# Qwiic_High_Performance_Magnetometer_X01.net
KiCad netlist of a schematic drawn in EAGLE
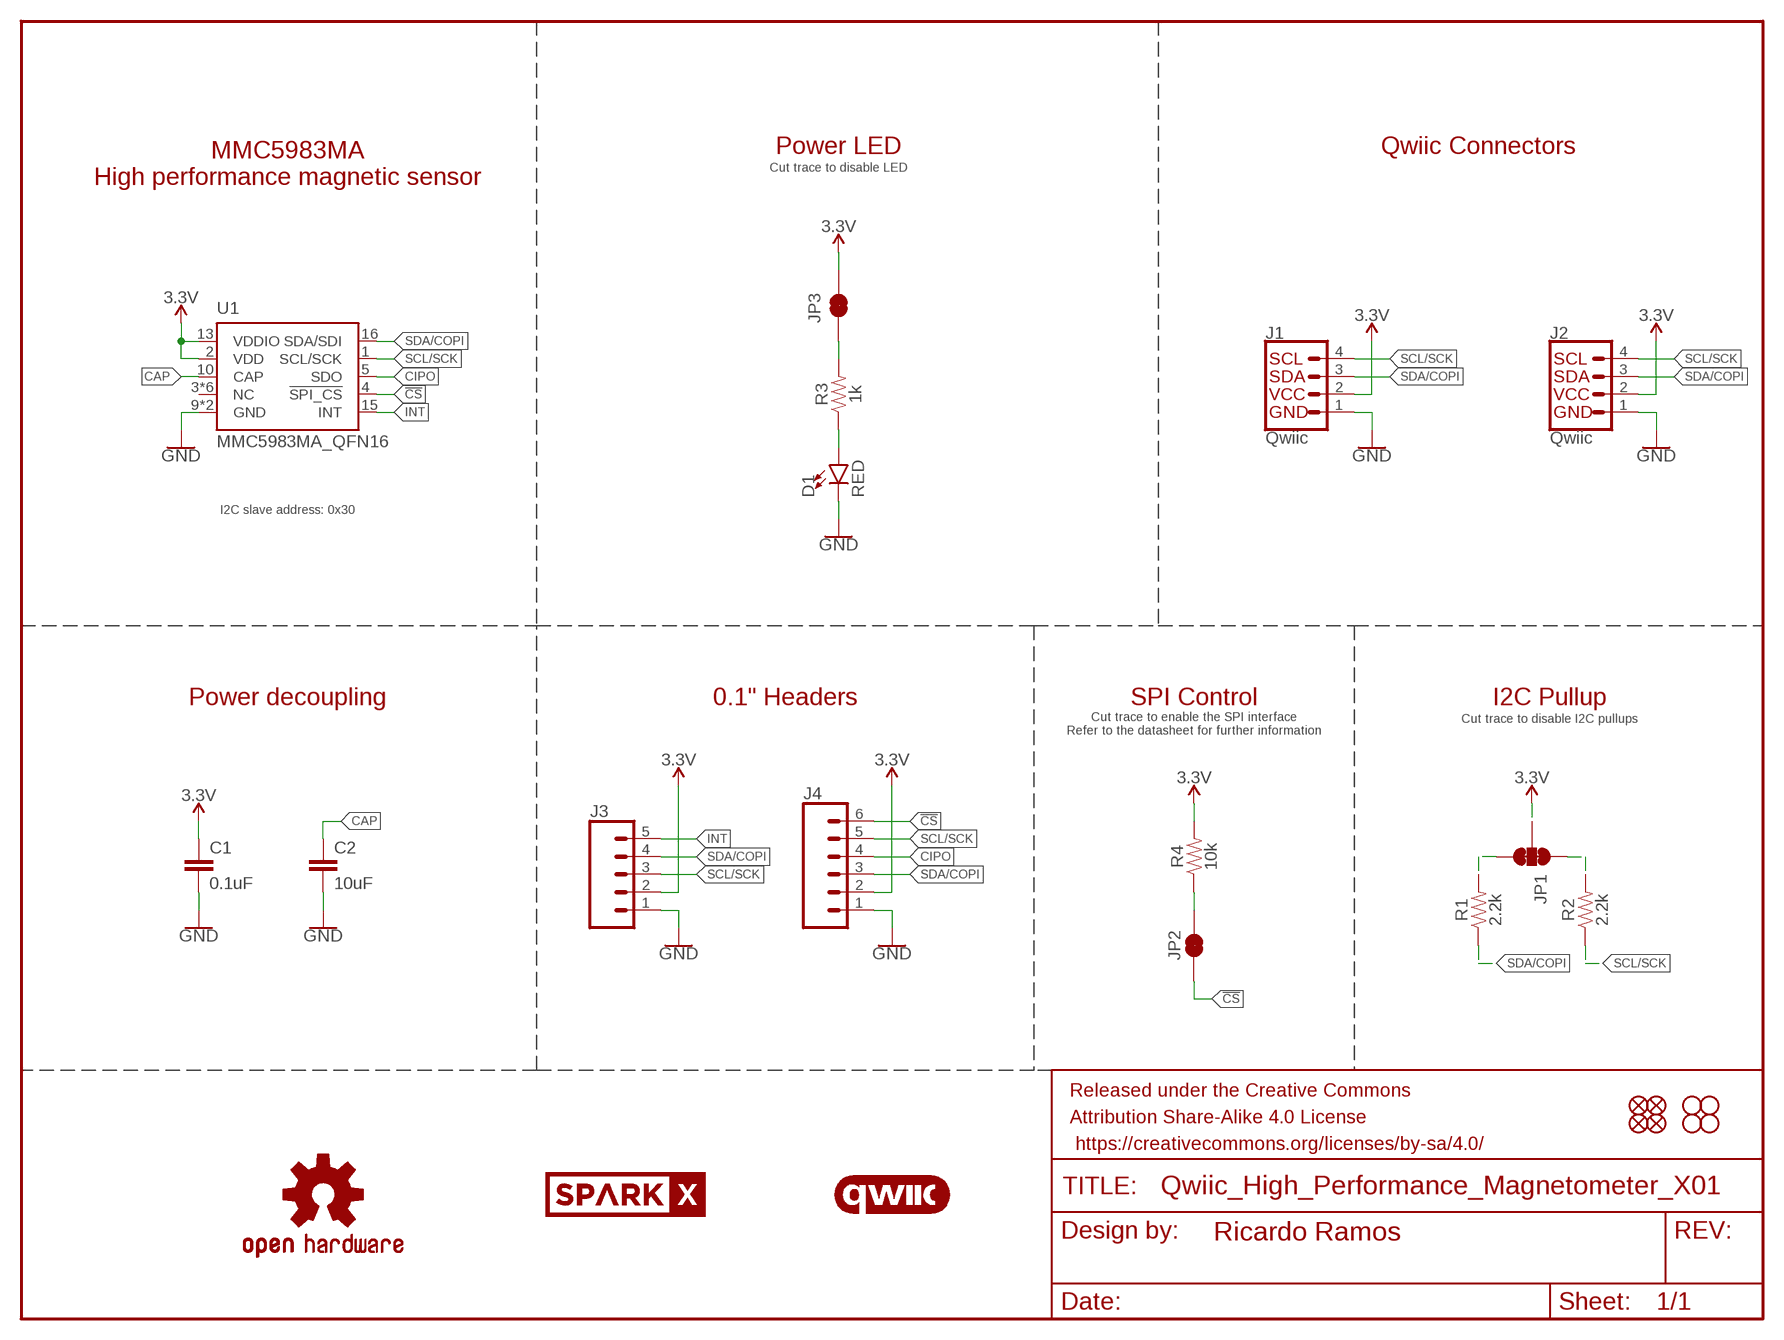
[diagram p0: schematic, sheet 1]

(export (version "E")
  (design (tool "Eeschema 10.0.6"))
  (components
    (comp (ref "C1")
      (value "0.1uF")
      (footprint "eagle-import:0603")
      (libsource (lib "eagle-import") (part "0.1UF-0603-25V-(+80/-20%)"))
    )
    (comp (ref "C2")
      (value "10uF")
      (footprint "eagle-import:0603")
      (libsource (lib "eagle-import") (part "10UF-0603-6.3V-20%"))
    )
    (comp (ref "D1")
      (value "RED")
      (footprint "eagle-import:LED-0603")
      (libsource (lib "eagle-import") (part "LED-RED0603"))
    )
    (comp (ref "FD1")
      (value "FIDUCIAL1X2")
      (footprint "eagle-import:FIDUCIAL-1X2")
      (libsource (lib "eagle-import") (part "FIDUCIAL1X2"))
    )
    (comp (ref "FD2")
      (value "FIDUCIAL1X2")
      (footprint "eagle-import:FIDUCIAL-1X2")
      (libsource (lib "eagle-import") (part "FIDUCIAL1X2"))
    )
    (comp (ref "FD3")
      (value "FIDUCIAL1X2")
      (footprint "eagle-import:FIDUCIAL-1X2")
      (libsource (lib "eagle-import") (part "FIDUCIAL1X2"))
    )
    (comp (ref "FD4")
      (value "FIDUCIAL1X2")
      (footprint "eagle-import:FIDUCIAL-1X2")
      (libsource (lib "eagle-import") (part "FIDUCIAL1X2"))
    )
    (comp (ref "FRAME1")
      (value "FRAME-LETTERNO_PACKAGE")
      (footprint "eagle-import:DUMMY")
      (fields (field (name "DESIGNER") "Ricardo Ramos") (field (name "DESIGNER_1") "Ricardo Ramos"))
      (libsource (lib "eagle-import") (part "FRAME-LETTERNO_PACKAGE"))
    )
    (comp (ref "H1")
      (value "STAND-OFF")
      (footprint "eagle-import:STAND-OFF")
      (libsource (lib "eagle-import") (part "STAND-OFF"))
    )
    (comp (ref "H2")
      (value "STAND-OFF")
      (footprint "eagle-import:STAND-OFF")
      (libsource (lib "eagle-import") (part "STAND-OFF"))
    )
    (comp (ref "H3")
      (value "STAND-OFF")
      (footprint "eagle-import:STAND-OFF")
      (libsource (lib "eagle-import") (part "STAND-OFF"))
    )
    (comp (ref "H4")
      (value "STAND-OFF")
      (footprint "eagle-import:STAND-OFF")
      (libsource (lib "eagle-import") (part "STAND-OFF"))
    )
    (comp (ref "J1")
      (value "Qwiic")
      (footprint "eagle-import:JST04_1MM_RA")
      (libsource (lib "eagle-import") (part "QWIIC_CONNECTORJS-1MM"))
    )
    (comp (ref "J2")
      (value "Qwiic")
      (footprint "eagle-import:JST04_1MM_RA")
      (libsource (lib "eagle-import") (part "QWIIC_CONNECTORJS-1MM"))
    )
    (comp (ref "J3")
      (value "CONN_05NO_SILK")
      (footprint "eagle-import:1X05_NO_SILK")
      (libsource (lib "eagle-import") (part "CONN_05NO_SILK"))
    )
    (comp (ref "J4")
      (value "CONN_06NO_SILK_NO_POP")
      (footprint "eagle-import:1X06_NO_SILK")
      (libsource (lib "eagle-import") (part "CONN_06NO_SILK_NO_POP"))
    )
    (comp (ref "JP1")
      (value "JUMPER-SMT_3_2-NC_TRACE_SILK")
      (footprint "eagle-import:SMT-JUMPER_3_2-NC_TRACE_SILK")
      (libsource (lib "eagle-import") (part "JUMPER-SMT_3_2-NC_TRACE_SILK"))
    )
    (comp (ref "JP2")
      (value "JUMPER-SMT_2_NC_TRACE_SILK")
      (footprint "eagle-import:SMT-JUMPER_2_NC_TRACE_SILK")
      (libsource (lib "eagle-import") (part "JUMPER-SMT_2_NC_TRACE_SILK"))
    )
    (comp (ref "JP3")
      (value "JUMPER-SMT_2_NC_TRACE_SILK")
      (footprint "eagle-import:SMT-JUMPER_2_NC_TRACE_SILK")
      (libsource (lib "eagle-import") (part "JUMPER-SMT_2_NC_TRACE_SILK"))
    )
    (comp (ref "LOGO1")
      (value "OSHW-LOGOMINI")
      (footprint "eagle-import:OSHW-LOGO-MINI")
      (libsource (lib "eagle-import") (part "OSHW-LOGOMINI"))
    )
    (comp (ref "LOGO2")
      (value "QWIIC_LOGO_5MM")
      (footprint "eagle-import:QWIIC_5MM")
      (libsource (lib "eagle-import") (part "QWIIC_LOGO_5MM"))
    )
    (comp (ref "R1")
      (value "2.2k")
      (footprint "eagle-import:0603")
      (libsource (lib "eagle-import") (part "2.2KOHM-0603-1/10W-1%"))
    )
    (comp (ref "R2")
      (value "2.2k")
      (footprint "eagle-import:0603")
      (libsource (lib "eagle-import") (part "2.2KOHM-0603-1/10W-1%"))
    )
    (comp (ref "R3")
      (value "1k")
      (footprint "eagle-import:0603")
      (libsource (lib "eagle-import") (part "1KOHM-0603-1/10W-1%"))
    )
    (comp (ref "R4")
      (value "10k")
      (footprint "eagle-import:0603")
      (libsource (lib "eagle-import") (part "10KOHM-0603-1/10W-1%"))
    )
    (comp (ref "U$36")
      (value "SPARKX-LOGO2")
      (footprint "eagle-import:SPARKX-TINY")
      (libsource (lib "eagle-import") (part "SPARKX-LOGO2"))
    )
    (comp (ref "U$37")
      (value "SPARKX-LOGO3")
      (footprint "eagle-import:SPARKX-SMALL")
      (libsource (lib "eagle-import") (part "SPARKX-LOGO3"))
    )
    (comp (ref "U1")
      (value "MMC5983MA_QFN16")
      (footprint "eagle-import:LGA-16-3X3MM-4X4PINS")
      (libsource (lib "eagle-import") (part "MMC5983MA_QFN16"))
    )
  )
  (nets
    (net (code "1") (name "/~{CS}") (class "Default")
      (node (ref "J4") (pin "6") (pinfunction "6_6") (pintype "passive"))
      (node (ref "JP2") (pin "1") (pinfunction "1_1") (pintype "passive"))
      (node (ref "U1") (pin "4") (pinfunction "~{SPI_CS}_4") (pintype "input"))
    )
    (net (code "2") (name "3.3V") (class "Default")
      (node (ref "C1") (pin "1") (pinfunction "1_1") (pintype "passive"))
      (node (ref "J1") (pin "2") (pinfunction "2_2") (pintype "power_in"))
      (node (ref "J2") (pin "2") (pinfunction "2_2") (pintype "power_in"))
      (node (ref "J3") (pin "2") (pinfunction "2_2") (pintype "passive"))
      (node (ref "J4") (pin "2") (pinfunction "2_2") (pintype "passive"))
      (node (ref "JP1") (pin "2") (pinfunction "2_2") (pintype "passive"))
      (node (ref "JP3") (pin "2") (pinfunction "2_2") (pintype "passive"))
      (node (ref "R4") (pin "2") (pinfunction "2_2") (pintype "passive"))
      (node (ref "U1") (pin "13") (pinfunction "VDDIO_13") (pintype "power_in"))
      (node (ref "U1") (pin "2") (pinfunction "VDD_2") (pintype "power_in"))
    )
    (net (code "3") (name "CAP") (class "Default")
      (node (ref "C2") (pin "1") (pinfunction "1_1") (pintype "passive"))
      (node (ref "U1") (pin "10") (pinfunction "CAP_10") (pintype "passive"))
    )
    (net (code "4") (name "CIPO") (class "Default")
      (node (ref "J4") (pin "4") (pinfunction "4_4") (pintype "passive"))
      (node (ref "U1") (pin "5") (pinfunction "SDO_5") (pintype "output"))
    )
    (net (code "5") (name "GND") (class "Default")
      (node (ref "C1") (pin "2") (pinfunction "2_2") (pintype "passive"))
      (node (ref "C2") (pin "2") (pinfunction "2_2") (pintype "passive"))
      (node (ref "D1") (pin "C") (pinfunction "C_C") (pintype "passive"))
      (node (ref "J1") (pin "1") (pinfunction "1_1") (pintype "power_in"))
      (node (ref "J2") (pin "1") (pinfunction "1_1") (pintype "power_in"))
      (node (ref "J3") (pin "1") (pinfunction "1_1") (pintype "passive"))
      (node (ref "J4") (pin "1") (pinfunction "1_1") (pintype "passive"))
      (node (ref "U1") (pin "11") (pinfunction "GND_11") (pintype "power_in"))
      (node (ref "U1") (pin "9") (pinfunction "GND_9") (pintype "power_in"))
    )
    (net (code "6") (name "INT") (class "Default")
      (node (ref "J3") (pin "5") (pinfunction "5_5") (pintype "passive"))
      (node (ref "U1") (pin "15") (pinfunction "INT_15") (pintype "output"))
    )
    (net (code "7") (name "Net-(D1-PadA)") (class "Default")
      (node (ref "D1") (pin "A") (pinfunction "A_A") (pintype "passive"))
      (node (ref "R3") (pin "1") (pinfunction "1_1") (pintype "passive"))
    )
    (net (code "8") (name "Net-(JP1-Pad1)") (class "Default")
      (node (ref "JP1") (pin "1") (pinfunction "1_1") (pintype "passive"))
      (node (ref "R2") (pin "2") (pinfunction "2_2") (pintype "passive"))
    )
    (net (code "9") (name "Net-(JP1-Pad3)") (class "Default")
      (node (ref "JP1") (pin "3") (pinfunction "3_3") (pintype "passive"))
      (node (ref "R1") (pin "2") (pinfunction "2_2") (pintype "passive"))
    )
    (net (code "10") (name "Net-(JP2-Pad2)") (class "Default")
      (node (ref "JP2") (pin "2") (pinfunction "2_2") (pintype "passive"))
      (node (ref "R4") (pin "1") (pinfunction "1_1") (pintype "passive"))
    )
    (net (code "11") (name "Net-(JP3-Pad1)") (class "Default")
      (node (ref "JP3") (pin "1") (pinfunction "1_1") (pintype "passive"))
      (node (ref "R3") (pin "2") (pinfunction "2_2") (pintype "passive"))
    )
    (net (code "12") (name "SCL{slash}SCK") (class "Default")
      (node (ref "J1") (pin "4") (pinfunction "4_4") (pintype "passive"))
      (node (ref "J2") (pin "4") (pinfunction "4_4") (pintype "passive"))
      (node (ref "J3") (pin "3") (pinfunction "3_3") (pintype "passive"))
      (node (ref "J4") (pin "5") (pinfunction "5_5") (pintype "passive"))
      (node (ref "R2") (pin "1") (pinfunction "1_1") (pintype "passive"))
      (node (ref "U1") (pin "1") (pinfunction "SCL/SCK_1") (pintype "bidirectional"))
    )
    (net (code "13") (name "SDA{slash}COPI") (class "Default")
      (node (ref "J1") (pin "3") (pinfunction "3_3") (pintype "passive"))
      (node (ref "J2") (pin "3") (pinfunction "3_3") (pintype "passive"))
      (node (ref "J3") (pin "4") (pinfunction "4_4") (pintype "passive"))
      (node (ref "J4") (pin "3") (pinfunction "3_3") (pintype "passive"))
      (node (ref "R1") (pin "1") (pinfunction "1_1") (pintype "passive"))
      (node (ref "U1") (pin "16") (pinfunction "SDA/SDI_16") (pintype "bidirectional"))
    )
    (net (code "14") (name "unconnected-(U1-NC-Pad3)") (class "Default")
      (node (ref "U1") (pin "3") (pinfunction "NC_3") (pintype "no_connect"))
    )
    (net (code "15") (name "unconnected-(U1-NC-Pad6)") (class "Default")
      (node (ref "U1") (pin "6") (pinfunction "NC_6") (pintype "no_connect"))
    )
    (net (code "16") (name "unconnected-(U1-NC-Pad7)") (class "Default")
      (node (ref "U1") (pin "7") (pinfunction "NC_7") (pintype "no_connect"))
    )
    (net (code "17") (name "unconnected-(U1-NC-Pad8)") (class "Default")
      (node (ref "U1") (pin "8") (pinfunction "NC_8") (pintype "no_connect"))
    )
    (net (code "18") (name "unconnected-(U1-NC-Pad12)") (class "Default")
      (node (ref "U1") (pin "12") (pinfunction "NC_12") (pintype "no_connect"))
    )
    (net (code "19") (name "unconnected-(U1-NC-Pad14)") (class "Default")
      (node (ref "U1") (pin "14") (pinfunction "NC_14") (pintype "no_connect"))
    )
  )
)
